# RS485.net
KiCad netlist of a schematic drawn in Altium Designer
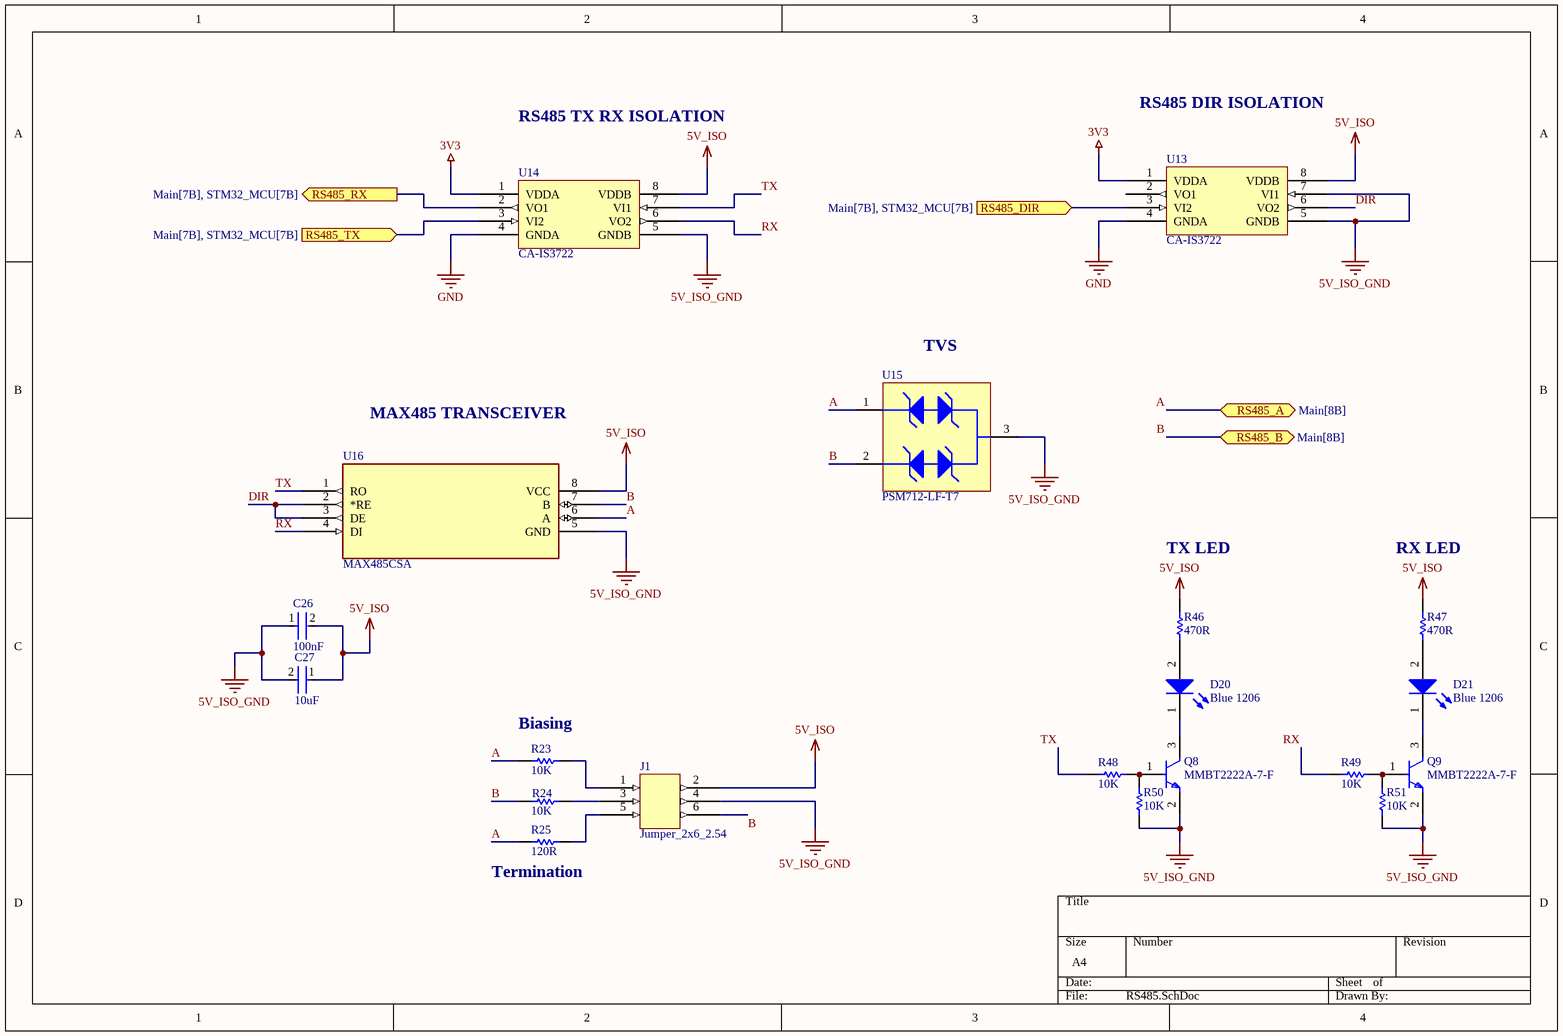
[diagram p0: RS485.SchDoc]

(export (version "E")
  (design (tool "Eeschema 10.0.6"))
  (components
    (comp (ref "C26")
      (value "100nF")
      (footprint "FP-CGA3E-0_3-0_1-IPC_A")
      (description "Cap Ceramic 100nF 50V X7R 10% Pad SMD 0603 +125°C Automotive T/R")
      (fields (field (name "TOLERANCE") "10%") (field (name "VOLTAGE") "50V"))
      (libsource (lib "Altium Content Vault") (part "b4654b650e69147ec39a6b967a45e02"))
    )
    (comp (ref "C27")
      (value "10uF")
      (footprint "FP-GRM188-0_1-e0_2_0_55-IPC_A")
      (description "Chip Multilayer Ceramic Capacitors for General Purpose, 0603, 10uF, X5R, 15%, 20%, 6.3V")
      (fields (field (name "VOLTAGE") "6.3V") (field (name "TOLERANCE") "20%"))
      (libsource (lib "Altium Content Vault") (part "02cd4be3c70576c341d710602a673aa"))
    )
    (comp (ref "D20")
      (value "Blue 1206")
      (footprint "WL-SMCW_1206_150120xx75000")
      (description "WL-SMCW SMT Mono-Color Chip LED Waterclear")
      (libsource (lib "Altium Content Vault") (part "LED_Blue_2A-1K"))
    )
    (comp (ref "D21")
      (value "Blue 1206")
      (footprint "WL-SMCW_1206_150120xx75000")
      (description "WL-SMCW SMT Mono-Color Chip LED Waterclear")
      (libsource (lib "Altium Content Vault") (part "LED_Blue_2A-1K"))
    )
    (comp (ref "J1")
      (value "Jumper_2x6_2.54")
      (footprint "Jumper_2x6_2.54")
      (libsource (lib "Jumper_2x6_2.54") (part "Jumper_2x6_2.54"))
    )
    (comp (ref "Q8")
      (value "MMBT2222A-7-F")
      (footprint "FP-SOT23-IPC_A")
      (description "TRANS NPN 40V 0.6A SMD SOT23-3")
      (fields (field (name "VOLTAGE") "40V"))
      (libsource (lib "Altium Content Vault") (part "b44e953556f554d0102664c7d152cb4"))
    )
    (comp (ref "Q9")
      (value "MMBT2222A-7-F")
      (footprint "FP-SOT23-IPC_A")
      (description "TRANS NPN 40V 0.6A SMD SOT23-3")
      (fields (field (name "VOLTAGE") "40V"))
      (libsource (lib "Altium Content Vault") (part "b44e953556f554d0102664c7d152cb4"))
    )
    (comp (ref "R23")
      (value "10K")
      (footprint "RESC1609X55X30LL15T15")
      (description "Chip Resistor, 10 KOhm, +/- 1%, 0.1 W, -55 to 155 degC, 0603 (1608 Metric), RoHS, Tape and Reel")
      (fields (field (name "TOLERANCE") "1%") (field (name "MANUFACTURER") "Panasonic"))
      (libsource (lib "Altium Content Vault") (part "RES-2"))
    )
    (comp (ref "R24")
      (value "10K")
      (footprint "RESC1609X55X30LL15T15")
      (description "Chip Resistor, 10 KOhm, +/- 1%, 0.1 W, -55 to 155 degC, 0603 (1608 Metric), RoHS, Tape and Reel")
      (fields (field (name "TOLERANCE") "1%") (field (name "MANUFACTURER") "Panasonic"))
      (libsource (lib "Altium Content Vault") (part "RES-2"))
    )
    (comp (ref "R25")
      (value "120R")
      (footprint "RESC1609X55X30ML15T15")
      (description "Chip Resistor, 120 Ohm, +/- 1%, 0.1 W, -55 to 155 degC, 0603 (1608 Metric), RoHS, Tape and Reel")
      (fields (field (name "TOLERANCE") "1%") (field (name "MANUFACTURER") "Panasonic"))
      (libsource (lib "Altium Content Vault") (part "RES-2"))
    )
    (comp (ref "R46")
      (value "470R")
      (footprint "RESC1608X55X30NL15T15")
      (fields (field (name "TOLERANCE") "5%"))
      (libsource (lib "Altium Content Vault") (part "RES-2"))
    )
    (comp (ref "R47")
      (value "470R")
      (footprint "RESC1608X55X30NL15T15")
      (fields (field (name "TOLERANCE") "5%"))
      (libsource (lib "Altium Content Vault") (part "RES-2"))
    )
    (comp (ref "R48")
      (value "10K")
      (footprint "RESC1609X55X30LL15T15")
      (description "Chip Resistor, 10 KOhm, +/- 1%, 0.1 W, -55 to 155 degC, 0603 (1608 Metric), RoHS, Tape and Reel")
      (fields (field (name "TOLERANCE") "1%") (field (name "MANUFACTURER") "Panasonic"))
      (libsource (lib "Altium Content Vault") (part "RES-2"))
    )
    (comp (ref "R49")
      (value "10K")
      (footprint "RESC1609X55X30LL15T15")
      (description "Chip Resistor, 10 KOhm, +/- 1%, 0.1 W, -55 to 155 degC, 0603 (1608 Metric), RoHS, Tape and Reel")
      (fields (field (name "TOLERANCE") "1%") (field (name "MANUFACTURER") "Panasonic"))
      (libsource (lib "Altium Content Vault") (part "RES-2"))
    )
    (comp (ref "R50")
      (value "10K")
      (footprint "RESC1609X55X30LL15T15")
      (description "Chip Resistor, 10 KOhm, +/- 1%, 0.1 W, -55 to 155 degC, 0603 (1608 Metric), RoHS, Tape and Reel")
      (fields (field (name "TOLERANCE") "1%") (field (name "MANUFACTURER") "Panasonic"))
      (libsource (lib "Altium Content Vault") (part "RES-2"))
    )
    (comp (ref "R51")
      (value "10K")
      (footprint "RESC1609X55X30LL15T15")
      (description "Chip Resistor, 10 KOhm, +/- 1%, 0.1 W, -55 to 155 degC, 0603 (1608 Metric), RoHS, Tape and Reel")
      (fields (field (name "TOLERANCE") "1%") (field (name "MANUFACTURER") "Panasonic"))
      (libsource (lib "Altium Content Vault") (part "RES-2"))
    )
    (comp (ref "U13")
      (value "CA-IS3722")
      (footprint "CA-IS3722HS")
      (description "Dual Channel Standard Digital Isolators")
      (libsource (lib "CA-IS3722HS") (part "CA-IS3722"))
    )
    (comp (ref "U14")
      (value "CA-IS3722")
      (footprint "CA-IS3722HS")
      (description "Dual Channel Standard Digital Isolators")
      (libsource (lib "CA-IS3722HS") (part "CA-IS3722"))
    )
    (comp (ref "U15")
      (value "PSM712-LF-T7")
      (footprint "PRKT-SOT23-3_V")
      (fields (field (name "MANUFACTURER") "Protek Devices") (field (name "VOLTAGE") "12V"))
      (libsource (lib "Altium Content Vault") (part "PRTK-PSM712-SOT23-3"))
    )
    (comp (ref "U16")
      (value "MAX485CSA")
      (footprint "21-0041B_8")
      (description "Low-Power, Slew-Rate-Limited RS-485/RS-422 Transceivers")
      (fields (field (name "MF") "Analog Devices") (field (name "MP") "MAX485CSA+"))
      (libsource (lib "MAX485CSA") (part "MAX485CSA"))
    )
  )
  (nets
    (net (code "1") (name "/A") (class "Default")
      (node (ref "R23") (pin "2") (pinfunction "2_2") (pintype "passive"))
      (node (ref "R25") (pin "1") (pinfunction "1_1") (pintype "passive"))
      (node (ref "U15") (pin "1") (pinfunction "1_1") (pintype "passive"))
      (node (ref "U16") (pin "6") (pinfunction "A_6") (pintype "bidirectional"))
    )
    (net (code "2") (name "/B") (class "Default")
      (node (ref "J1") (pin "6") (pintype "output"))
      (node (ref "R24") (pin "2") (pinfunction "2_2") (pintype "passive"))
      (node (ref "U15") (pin "2") (pinfunction "2_2") (pintype "passive"))
      (node (ref "U16") (pin "7") (pinfunction "B_7") (pintype "bidirectional"))
    )
    (net (code "3") (name "/DIR") (class "Default")
      (node (ref "U13") (pin "6") (pinfunction "VO2_6") (pintype "output"))
      (node (ref "U16") (pin "2") (pinfunction "*RE_2") (pintype "output"))
      (node (ref "U16") (pin "3") (pinfunction "DE_3") (pintype "output"))
    )
    (net (code "4") (name "/RS485_DIR") (class "Default")
      (node (ref "U13") (pin "3") (pinfunction "VI2_3") (pintype "input"))
    )
    (net (code "5") (name "/RS485_RX") (class "Default")
      (node (ref "U14") (pin "2") (pinfunction "VO1_2") (pintype "output"))
    )
    (net (code "6") (name "/RS485_TX") (class "Default")
      (node (ref "U14") (pin "3") (pinfunction "VI2_3") (pintype "input"))
    )
    (net (code "7") (name "/RX") (class "Default")
      (node (ref "R49") (pin "2") (pinfunction "2_2") (pintype "passive"))
      (node (ref "U14") (pin "6") (pinfunction "VO2_6") (pintype "output"))
      (node (ref "U16") (pin "4") (pinfunction "DI_4") (pintype "input"))
    )
    (net (code "8") (name "/TX") (class "Default")
      (node (ref "R48") (pin "2") (pinfunction "2_2") (pintype "passive"))
      (node (ref "U14") (pin "7") (pinfunction "VI1_7") (pintype "input"))
      (node (ref "U16") (pin "1") (pinfunction "RO_1") (pintype "output"))
    )
    (net (code "9") (name "3V3") (class "Default")
      (node (ref "U13") (pin "1") (pinfunction "VDDA_1") (pintype "power_in"))
      (node (ref "U14") (pin "1") (pinfunction "VDDA_1") (pintype "power_in"))
    )
    (net (code "10") (name "5V_ISO") (class "Default")
      (node (ref "C26") (pin "2") (pinfunction "2_2") (pintype "passive"))
      (node (ref "C27") (pin "1") (pinfunction "1_1") (pintype "passive"))
      (node (ref "J1") (pin "2") (pintype "output"))
      (node (ref "R46") (pin "1") (pinfunction "1_1") (pintype "passive"))
      (node (ref "R47") (pin "1") (pinfunction "1_1") (pintype "passive"))
      (node (ref "U13") (pin "8") (pinfunction "VDDB_8") (pintype "power_in"))
      (node (ref "U14") (pin "8") (pinfunction "VDDB_8") (pintype "power_in"))
      (node (ref "U16") (pin "8") (pinfunction "VCC_8") (pintype "power_in"))
    )
    (net (code "11") (name "5V_ISO_GND") (class "Default")
      (node (ref "C26") (pin "1") (pinfunction "1_1") (pintype "passive"))
      (node (ref "C27") (pin "2") (pinfunction "2_2") (pintype "passive"))
      (node (ref "J1") (pin "4") (pintype "output"))
      (node (ref "Q8") (pin "2") (pinfunction "E_2") (pintype "passive"))
      (node (ref "Q9") (pin "2") (pinfunction "E_2") (pintype "passive"))
      (node (ref "R50") (pin "1") (pinfunction "1_1") (pintype "passive"))
      (node (ref "R51") (pin "1") (pinfunction "1_1") (pintype "passive"))
      (node (ref "U13") (pin "5") (pinfunction "GNDB_5") (pintype "power_in"))
      (node (ref "U13") (pin "7") (pinfunction "VI1_7") (pintype "input"))
      (node (ref "U14") (pin "5") (pinfunction "GNDB_5") (pintype "power_in"))
      (node (ref "U15") (pin "3") (pinfunction "3_3") (pintype "passive"))
      (node (ref "U16") (pin "5") (pinfunction "GND_5") (pintype "power_in"))
    )
    (net (code "12") (name "GND") (class "Default")
      (node (ref "U13") (pin "4") (pinfunction "GNDA_4") (pintype "power_in"))
      (node (ref "U14") (pin "4") (pinfunction "GNDA_4") (pintype "power_in"))
    )
    (net (code "13") (name "Net-(D20-A)") (class "Default")
      (node (ref "D20") (pin "2") (pinfunction "A_2") (pintype "passive"))
      (node (ref "R46") (pin "2") (pinfunction "2_2") (pintype "passive"))
    )
    (net (code "14") (name "Net-(D20-K)") (class "Default")
      (node (ref "D20") (pin "1") (pinfunction "K_1") (pintype "passive"))
      (node (ref "Q8") (pin "3") (pinfunction "C_3") (pintype "passive"))
    )
    (net (code "15") (name "Net-(D21-A)") (class "Default")
      (node (ref "D21") (pin "2") (pinfunction "A_2") (pintype "passive"))
      (node (ref "R47") (pin "2") (pinfunction "2_2") (pintype "passive"))
    )
    (net (code "16") (name "Net-(D21-K)") (class "Default")
      (node (ref "D21") (pin "1") (pinfunction "K_1") (pintype "passive"))
      (node (ref "Q9") (pin "3") (pinfunction "C_3") (pintype "passive"))
    )
    (net (code "17") (name "Net-(J1-Pad1)") (class "Default")
      (node (ref "J1") (pin "1") (pintype "input"))
      (node (ref "R23") (pin "1") (pinfunction "1_1") (pintype "passive"))
    )
    (net (code "18") (name "Net-(J1-Pad3)") (class "Default")
      (node (ref "J1") (pin "3") (pintype "input"))
      (node (ref "R24") (pin "1") (pinfunction "1_1") (pintype "passive"))
    )
    (net (code "19") (name "Net-(J1-Pad5)") (class "Default")
      (node (ref "J1") (pin "5") (pintype "input"))
      (node (ref "R25") (pin "2") (pinfunction "2_2") (pintype "passive"))
    )
    (net (code "20") (name "Net-(Q8-B)") (class "Default")
      (node (ref "Q8") (pin "1") (pinfunction "B_1") (pintype "passive"))
      (node (ref "R48") (pin "1") (pinfunction "1_1") (pintype "passive"))
      (node (ref "R50") (pin "2") (pinfunction "2_2") (pintype "passive"))
    )
    (net (code "21") (name "Net-(Q9-B)") (class "Default")
      (node (ref "Q9") (pin "1") (pinfunction "B_1") (pintype "passive"))
      (node (ref "R49") (pin "1") (pinfunction "1_1") (pintype "passive"))
      (node (ref "R51") (pin "2") (pinfunction "2_2") (pintype "passive"))
    )
    (net (code "22") (name "unconnected-(U13-VO1-Pad2)") (class "Default")
      (node (ref "U13") (pin "2") (pinfunction "VO1_2") (pintype "output"))
    )
  )
)
